# Interface.net
KiCad netlist of a schematic drawn in Altium Designer
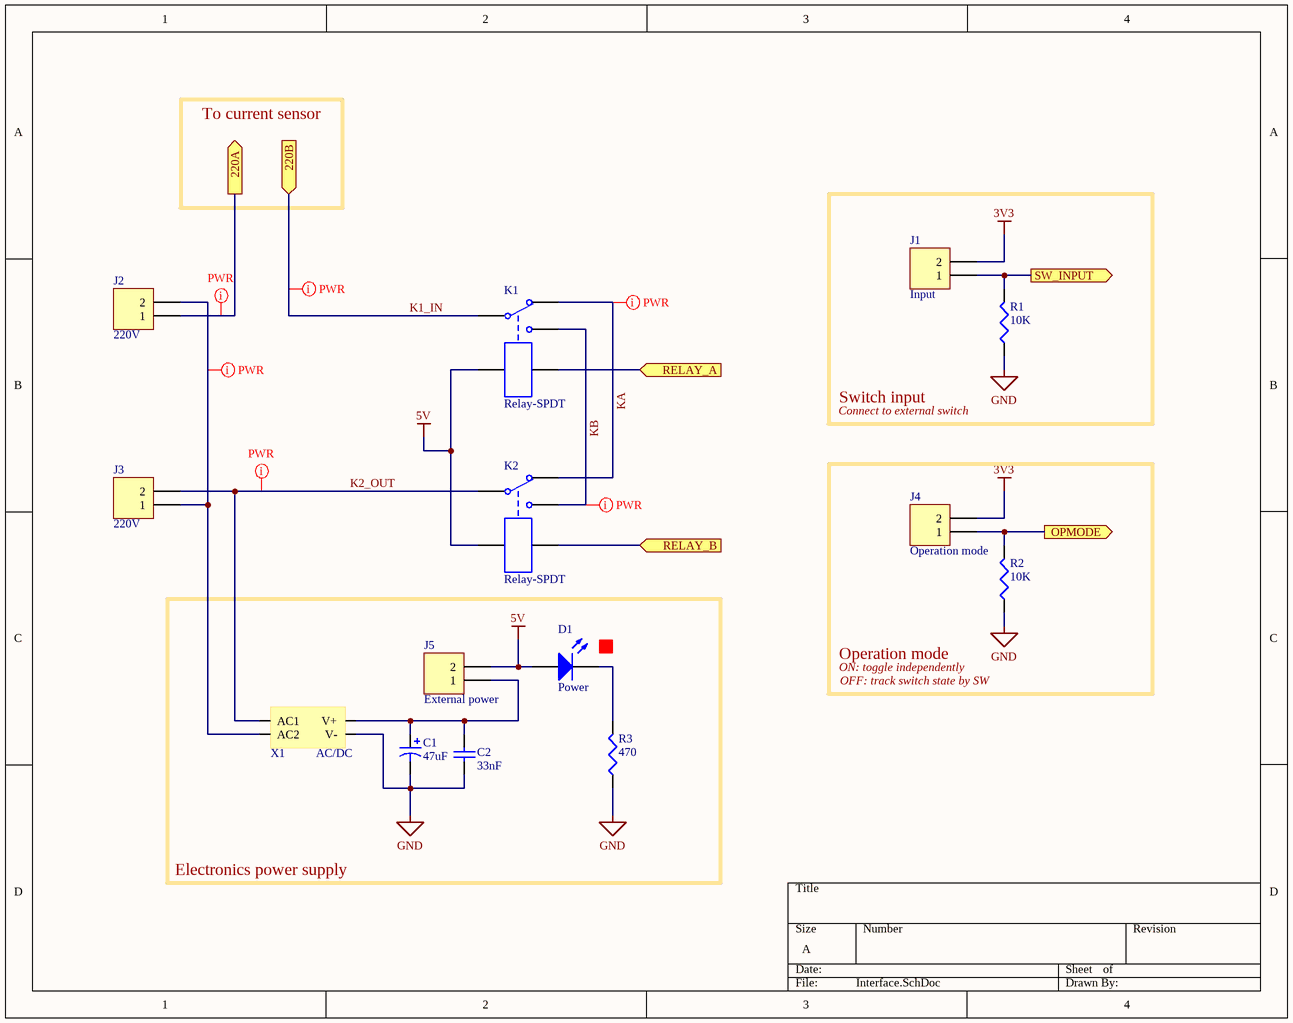
[diagram p0: Interface.SchDoc]

(export (version "E")
  (design (tool "Eeschema 10.0.6"))
  (components
    (comp (ref "C1")
      (value "47uF")
      (footprint "CAP47U")
      (description "Polarized Capacitor (Radial)")
      (fields
        (field (name "TOLERANCE") "20%")
        (field (name "Comment") "Cap Pol1")
        (field (name "PUBLISHER") "Altium Limited")
      )
      (libsource (lib "Miscellaneous Devices") (part "Cap Pol1"))
    )
    (comp (ref "C2")
      (value "33nF")
      (footprint "C0805")
      (description "Capacitor")
      (fields
        (field (name "TOLERANCE") "10%")
        (field (name "VOLTAGE") "50V")
        (field (name "PUBLISHER") "Altium Limited")
      )
      (libsource (lib "Miscellaneous Devices") (part "Cap"))
    )
    (comp (ref "D1")
      (value "Power")
      (footprint "3.2X1.6X1.1")
      (description "Typical RED, GREEN, YELLOW, AMBER GaAs LED")
      (fields (field (name "PUBLISHER") "Altium Limited"))
      (libsource (lib "Miscellaneous Devices") (part "LED2"))
    )
    (comp (ref "J1")
      (value "Input")
      (footprint "TBLOCK2")
      (description "Header, 2-Pin")
      (fields (field (name "VOLTAGE") "150V") (field (name "PUBLISHER") "Altium Limited"))
      (libsource (lib "Miscellaneous Connectors") (part "Header 2"))
    )
    (comp (ref "J2")
      (value "220V")
      (footprint "TBLOCK2")
      (description "Header, 2-Pin")
      (fields (field (name "VOLTAGE") "150V") (field (name "PUBLISHER") "Altium Limited"))
      (libsource (lib "Miscellaneous Connectors") (part "Header 2"))
    )
    (comp (ref "J3")
      (value "220V")
      (footprint "TBLOCK2")
      (description "Header, 2-Pin")
      (fields (field (name "VOLTAGE") "150V") (field (name "PUBLISHER") "Altium Limited"))
      (libsource (lib "Miscellaneous Connectors") (part "Header 2"))
    )
    (comp (ref "J4")
      (value "Operation mode")
      (footprint "HEADER2")
      (description "Header, 2-Pin")
      (fields (field (name "PUBLISHER") "Altium Limited"))
      (libsource (lib "Miscellaneous Connectors") (part "Header 2"))
    )
    (comp (ref "J5")
      (value "External power")
      (footprint "HEADER2")
      (description "Header, 2-Pin")
      (fields (field (name "PUBLISHER") "Altium Limited"))
      (libsource (lib "Miscellaneous Connectors") (part "Header 2"))
    )
    (comp (ref "K1")
      (value "Relay-SPDT")
      (footprint "G5LE-1C")
      (description "Single-Pole Dual-Throw Relay")
      (fields (field (name "PUBLISHER") "Altium Limited"))
      (libsource (lib "Miscellaneous Devices") (part "Relay-SPDT"))
    )
    (comp (ref "K2")
      (value "Relay-SPDT")
      (footprint "G5LE-1C")
      (description "Single-Pole Dual-Throw Relay")
      (fields (field (name "PUBLISHER") "Altium Limited"))
      (libsource (lib "Miscellaneous Devices") (part "Relay-SPDT"))
    )
    (comp (ref "R1")
      (value "10K")
      (footprint "J1-0603")
      (description "Resistor")
      (fields
        (field (name "TOLERANCE") "5%")
        (field (name "Comment") "Res3")
        (field (name "PUBLISHER") "Altium Limited")
      )
      (libsource (lib "Miscellaneous Devices") (part "Res3"))
    )
    (comp (ref "R2")
      (value "10K")
      (footprint "J1-0603")
      (description "Resistor")
      (fields
        (field (name "TOLERANCE") "5%")
        (field (name "Comment") "Res3")
        (field (name "PUBLISHER") "Altium Limited")
      )
      (libsource (lib "Miscellaneous Devices") (part "Res3"))
    )
    (comp (ref "R3")
      (value "470")
      (footprint "J1-0603")
      (description "Resistor")
      (fields
        (field (name "TOLERANCE") "5%")
        (field (name "Comment") "Res3")
        (field (name "PUBLISHER") "Altium Limited")
      )
      (libsource (lib "Miscellaneous Devices") (part "Res3"))
    )
    (comp (ref "X1")
      (value "AC/DC")
      (footprint "HLK-PM01")
      (description "220Vac to 5Vdc converter (3W)")
      (libsource (lib "SmartplugComponents") (part "HLK-PM01"))
    )
  )
  (nets
    (net (code "1") (name "/220A") (class "Default")
      (node (ref "J2") (pin "1") (pinfunction "1_1") (pintype "passive"))
    )
    (net (code "2") (name "/K1_IN") (class "Default")
      (node (ref "K1") (pin "1") (pinfunction "1_1") (pintype "passive"))
    )
    (net (code "3") (name "/K2_OUT") (class "Default")
      (node (ref "J3") (pin "2") (pinfunction "2_2") (pintype "passive"))
      (node (ref "K2") (pin "1") (pinfunction "1_1") (pintype "passive"))
      (node (ref "X1") (pin "1") (pinfunction "AC1_1") (pintype "passive"))
    )
    (net (code "4") (name "/KA") (class "Default")
      (node (ref "K1") (pin "2") (pinfunction "2_2") (pintype "passive"))
      (node (ref "K2") (pin "2") (pinfunction "2_2") (pintype "passive"))
    )
    (net (code "5") (name "/KB") (class "Default")
      (node (ref "K1") (pin "3") (pinfunction "3_3") (pintype "passive"))
      (node (ref "K2") (pin "3") (pinfunction "3_3") (pintype "passive"))
    )
    (net (code "6") (name "/OPMODE") (class "Default")
      (node (ref "J4") (pin "1") (pinfunction "1_1") (pintype "passive"))
      (node (ref "R2") (pin "2") (pinfunction "2_2") (pintype "passive"))
    )
    (net (code "7") (name "/RELAY_A") (class "Default")
      (node (ref "K1") (pin "5") (pinfunction "5_5") (pintype "passive"))
    )
    (net (code "8") (name "/RELAY_B") (class "Default")
      (node (ref "K2") (pin "5") (pinfunction "5_5") (pintype "passive"))
    )
    (net (code "9") (name "/SW_INPUT") (class "Default")
      (node (ref "J1") (pin "1") (pinfunction "1_1") (pintype "passive"))
      (node (ref "R1") (pin "2") (pinfunction "2_2") (pintype "passive"))
    )
    (net (code "10") (name "3V3") (class "Default")
      (node (ref "J1") (pin "2") (pinfunction "2_2") (pintype "passive"))
      (node (ref "J4") (pin "2") (pinfunction "2_2") (pintype "passive"))
    )
    (net (code "11") (name "5V") (class "Default")
      (node (ref "D1") (pin "1") (pinfunction "A_1") (pintype "passive"))
      (node (ref "J5") (pin "2") (pinfunction "2_2") (pintype "passive"))
      (node (ref "K1") (pin "4") (pinfunction "4_4") (pintype "passive"))
      (node (ref "K2") (pin "4") (pinfunction "4_4") (pintype "passive"))
    )
    (net (code "12") (name "GND") (class "Default")
      (node (ref "C1") (pin "2") (pinfunction "2_2") (pintype "passive"))
      (node (ref "C2") (pin "1") (pinfunction "1_1") (pintype "passive"))
      (node (ref "R1") (pin "1") (pinfunction "1_1") (pintype "passive"))
      (node (ref "R2") (pin "1") (pinfunction "1_1") (pintype "passive"))
      (node (ref "R3") (pin "1") (pinfunction "1_1") (pintype "passive"))
      (node (ref "X1") (pin "3") (pinfunction "V-_3") (pintype "passive"))
    )
    (net (code "13") (name "Net-(D1-K)") (class "Default")
      (node (ref "D1") (pin "2") (pinfunction "K_2") (pintype "passive"))
      (node (ref "R3") (pin "2") (pinfunction "2_2") (pintype "passive"))
    )
    (net (code "14") (name "Net-(X1-AC2)") (class "Default")
      (node (ref "J2") (pin "2") (pinfunction "2_2") (pintype "passive"))
      (node (ref "J3") (pin "1") (pinfunction "1_1") (pintype "passive"))
      (node (ref "X1") (pin "2") (pinfunction "AC2_2") (pintype "passive"))
    )
    (net (code "15") (name "Net-(X1-V+)") (class "Default")
      (node (ref "C1") (pin "1") (pinfunction "1_1") (pintype "passive"))
      (node (ref "C2") (pin "2") (pinfunction "2_2") (pintype "passive"))
      (node (ref "J5") (pin "1") (pinfunction "1_1") (pintype "passive"))
      (node (ref "X1") (pin "4") (pinfunction "V+_4") (pintype "passive"))
    )
  )
)
